# Bluetooth.net
KiCad netlist of a schematic drawn in Altium Designer
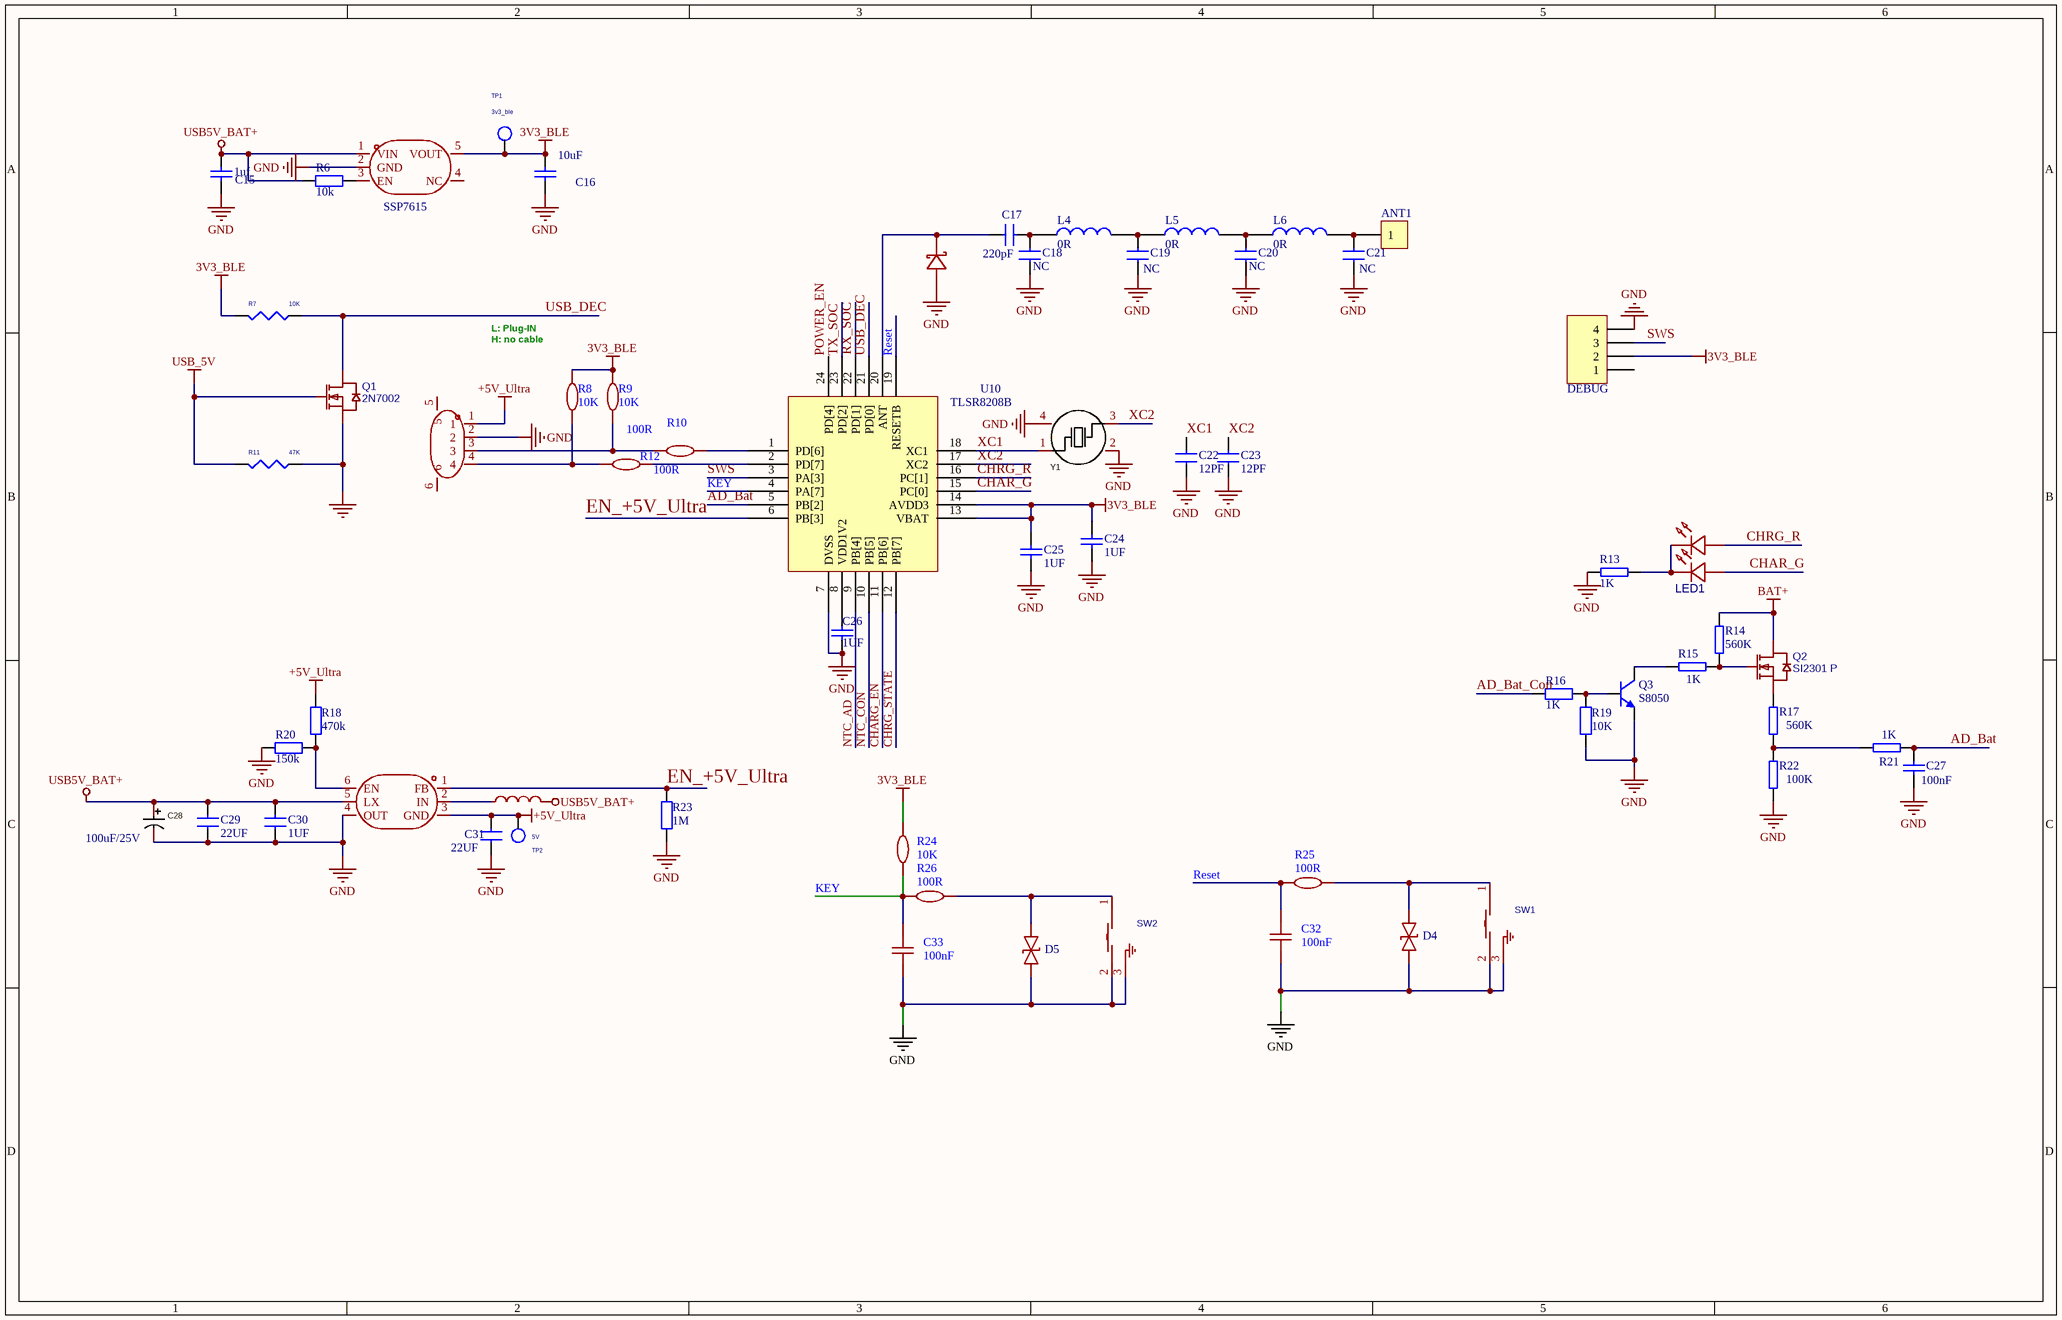
[diagram p0: Bluetooth.SchDoc]

(export (version "E")
  (design (tool "Eeschema 10.0.6"))
  (components
    (comp (ref "ANT1")
      (value "~")
      (footprint "tp")
      (description "Connector")
      (libsource (lib "*") (part "CON1"))
    )
    (comp (ref "C15")
      (value "1uf")
      (footprint "0603_C")
      (description "无极电容")
      (libsource (lib "电容电阻电感保险") (part "Cap1"))
    )
    (comp (ref "C16")
      (value "10uF")
      (footprint "0603_C")
      (description "Capacitor")
      (fields (field (name "PUBLISHER") "Altium Limited"))
      (libsource (lib "*") (part "Cap"))
    )
    (comp (ref "C17")
      (value "220pF")
      (footprint "0402_c")
      (description "Capacitor")
      (libsource (lib "*") (part "CAP"))
    )
    (comp (ref "C18")
      (value "NC")
      (footprint "0402_C")
      (description "Capacitor")
      (libsource (lib "*") (part "CAP"))
    )
    (comp (ref "C19")
      (value "NC")
      (footprint "0402_C")
      (description "Capacitor")
      (libsource (lib "*") (part "CAP"))
    )
    (comp (ref "C20")
      (value "NC")
      (footprint "0402_C")
      (description "Capacitor")
      (libsource (lib "*") (part "CAP"))
    )
    (comp (ref "C21")
      (value "NC")
      (footprint "0402_C")
      (description "Capacitor")
      (libsource (lib "*") (part "CAP"))
    )
    (comp (ref "C22")
      (value "12PF")
      (footprint "0603_c")
      (description "Capacitor")
      (libsource (lib "*") (part "CAP"))
    )
    (comp (ref "C23")
      (value "12PF")
      (footprint "0603_c")
      (description "Capacitor")
      (libsource (lib "*") (part "CAP"))
    )
    (comp (ref "C24") (value "1UF") (footprint "0603_c") (libsource (lib "DIY") (part "CAP")))
    (comp (ref "C25") (value "1UF") (footprint "0603_c") (libsource (lib "DIY") (part "CAP")))
    (comp (ref "C26") (value "1UF") (footprint "0603_c") (libsource (lib "DIY") (part "CAP")))
    (comp (ref "C27") (value "100nF") (footprint "c0402") (libsource (lib "DIY") (part "CAP")))
    (comp (ref "C28")
      (value "100uF/25V")
      (footprint "SMD 6.3*5.4 电解")
      (fields (field (name "MANUFACTURER PART") "RVT1A221M0605"))
      (libsource (lib "altium-import") (part "root_0_RVT1A221M0605_C72494_"))
    )
    (comp (ref "C29")
      (value "22UF")
      (footprint "0805_c")
      (description "Capacitor")
      (libsource (lib "*") (part "CAP"))
    )
    (comp (ref "C30")
      (value "1UF")
      (footprint "0402_c")
      (description "Capacitor")
      (libsource (lib "*") (part "CAP"))
    )
    (comp (ref "C31")
      (value "22UF")
      (footprint "0805_c")
      (description "Capacitor")
      (libsource (lib "*") (part "CAP"))
    )
    (comp (ref "C32")
      (value "100nF")
      (footprint "c0402")
      (libsource (lib "altium-import") (part "root_1_CAP_0603_"))
    )
    (comp (ref "C33")
      (value "100nF")
      (footprint "c0402")
      (libsource (lib "altium-import") (part "root_1_CAP_0603_"))
    )
    (comp (ref "CON4")
      (value "Ultra")
      (footprint "CONN-SMD_4P-P1.25_LT")
      (libsource (lib "altium-import") (part "root_0_mirrored_HC-1.25-4PLT_"))
    )
    (comp (ref "D3")
      (value "SE6V3LHN102T 6.3v单向")
      (footprint "0402-D")
      (libsource (lib "altium-import") (part "root_3_TPNSR05F20NXT5G_"))
    )
    (comp (ref "D4")
      (value "LESD5Z5.0CT1G")
      (footprint "SOD-523_L1.2-W0.8-LS1.6-BI")
      (libsource (lib "altium-import") (part "root_1_LESD5Z5.0CT1G_"))
    )
    (comp (ref "D5")
      (value "LESD5Z5.0CT1G")
      (footprint "SOD-523_L1.2-W0.8-LS1.6-BI")
      (libsource (lib "altium-import") (part "root_1_LESD5Z5.0CT1G_"))
    )
    (comp (ref "L4") (value "0R") (footprint "0402_R") (libsource (lib "*") (part "INDUCTOR")))
    (comp (ref "L5") (value "0R") (footprint "0402_R") (libsource (lib "*") (part "INDUCTOR")))
    (comp (ref "L6") (value "0R") (footprint "0402_R") (libsource (lib "*") (part "INDUCTOR")))
    (comp (ref "L7")
      (value "SLW3012P1R5MST SMD3.0*3.0")
      (footprint "IND-SMD_L3.0-W3.0")
      (libsource (lib "altium-import") (part "root_0_SLW3012P1R5MST_"))
    )
    (comp (ref "LED1")
      (value "*")
      (footprint "LED-SMD_4P-L3.2-W1.6-TL_XL-3216SURUGC")
      (libsource (lib "altium-import") (part "root_0_TJ-S2012SW8TCGLC2R2G-A5_"))
    )
    (comp (ref "P1")
      (value "DEBUG")
      (footprint "SIP4-2.54")
      (description "Header, 4-Pin")
      (fields (field (name "PUBLISHER") "Altium Limited"))
      (libsource (lib "Miscellaneous Connectors") (part "Header 4"))
    )
    (comp (ref "Q1")
      (value "2N7002")
      (footprint "SOT-23")
      (fields
        (field (name "BOM_SUPPLIER PART") "C2890442")
        (field (name "BOM_MANUFACTURER PART") "JMTL3400A")
        (field (name "CONTRIBUTOR") "LCSC")
      )
      (libsource (lib "altium-import") (part "root_0_JMTL3400A_"))
    )
    (comp (ref "Q2")
      (value "SI2301 P")
      (footprint "SOT-23")
      (fields
        (field (name "BOM_SUPPLIER PART") "C2890442")
        (field (name "BOM_MANUFACTURER PART") "JMTL3400A")
        (field (name "CONTRIBUTOR") "LCSC")
      )
      (libsource (lib "") (part "root_0_JMTL3400A__1"))
    )
    (comp (ref "Q3")
      (value "S8050")
      (footprint "SOT-23(SOT-23-3)")
      (description "NPN三极管")
      (libsource (lib "二三极管mos可控硅") (part "NPN_sot23"))
    )
    (comp (ref "R6")
      (value "10k")
      (footprint "R0402")
      (description "Resistor")
      (fields (field (name "PUBLISHER") "Altium Limited"))
      (libsource (lib "") (part "Res2_3"))
    )
    (comp (ref "R7") (value "10K") (footprint "R0402") (libsource (lib "*") (part "R_Dup2")))
    (comp (ref "R8")
      (value "10K")
      (footprint "R0402")
      (libsource (lib "altium-import") (part "root_3_Res_0603_"))
    )
    (comp (ref "R9")
      (value "10K")
      (footprint "R0402")
      (libsource (lib "altium-import") (part "root_3_Res_0603_"))
    )
    (comp (ref "R10")
      (value "100R")
      (footprint "R0402")
      (libsource (lib "altium-import") (part "root_2_Res_0603_"))
    )
    (comp (ref "R11") (value "47K") (footprint "R0402") (libsource (lib "*") (part "R_Dup2")))
    (comp (ref "R12")
      (value "100R")
      (footprint "R0402")
      (libsource (lib "altium-import") (part "root_2_Res_0603_"))
    )
    (comp (ref "R13") (value "1K") (footprint "0603_R") (libsource (lib "DIY") (part "RES")))
    (comp (ref "R14") (value "560K") (footprint "R0402") (libsource (lib "") (part "RES_1")))
    (comp (ref "R15") (value "1K") (footprint "R0402") (libsource (lib "*") (part "RES")))
    (comp (ref "R16")
      (value "1K")
      (footprint "R0402")
      (description "Resistor")
      (fields (field (name "PUBLISHER") "Altium Limited"))
      (libsource (lib "") (part "Res2_1"))
    )
    (comp (ref "R17") (value "560K") (footprint "R0402") (libsource (lib "DIY") (part "RES")))
    (comp (ref "R18")
      (value "470k")
      (footprint "0402_r")
      (description "Resistor")
      (fields (field (name "PUBLISHER") "Altium Limited"))
      (libsource (lib "") (part "Res2_2"))
    )
    (comp (ref "R19")
      (value "10K")
      (footprint "R0402")
      (description "Resistor")
      (fields (field (name "PUBLISHER") "Altium Limited"))
      (libsource (lib "") (part "Res2_3"))
    )
    (comp (ref "R20")
      (value "150k")
      (footprint "0402_r")
      (description "Resistor")
      (fields (field (name "PUBLISHER") "Altium Limited"))
      (libsource (lib "*") (part "Res2"))
    )
    (comp (ref "R21") (value "1K") (footprint "R0402") (libsource (lib "DIY") (part "RES")))
    (comp (ref "R22") (value "100K") (footprint "R0402") (libsource (lib "DIY") (part "RES")))
    (comp (ref "R23")
      (value "1M")
      (footprint "0402_r")
      (description "Resistor")
      (fields (field (name "PUBLISHER") "Altium Limited"))
      (libsource (lib "") (part "Res2_2"))
    )
    (comp (ref "R24")
      (value "10K")
      (footprint "R0402")
      (libsource (lib "altium-import") (part "root_1_Res_0603_"))
    )
    (comp (ref "R25")
      (value "100R")
      (footprint "R0402")
      (libsource (lib "altium-import") (part "root_2_Res_0603_"))
    )
    (comp (ref "R26")
      (value "100R")
      (footprint "R0402")
      (libsource (lib "altium-import") (part "root_2_Res_0603_"))
    )
    (comp (ref "SW1")
      (value "Reset")
      (footprint "SMD-KEY-3")
      (libsource (lib "altium-import") (part "root_1_K2-1109SE-I4SW-04_"))
    )
    (comp (ref "SW2")
      (value "OnOff")
      (footprint "SMD-KEY-3")
      (libsource (lib "altium-import") (part "root_1_K2-1109SE-I4SW-04_"))
    )
    (comp (ref "TP1") (value "3v3_ble") (footprint "TP") (libsource (lib "*") (part "T POINT R")))
    (comp (ref "TP2") (value "5V") (footprint "TP") (libsource (lib "*") (part "T POINT R")))
    (comp (ref "U2")
      (value "SSP7615")
      (footprint "SOT-23-5")
      (libsource (lib "altium-import") (part "root_0_SSP7615-33M5R_"))
    )
    (comp (ref "U3")
      (value "SY7069ADC")
      (footprint "SOT-23-6")
      (libsource (lib "altium-import") (part "root_0_mirrored_SY7069ADC_"))
    )
    (comp (ref "U10")
      (value "TLSR8208B")
      (footprint "QFN-24-EP(4*4)")
      (libsource (lib "MyLib") (part "TLSR8208B"))
    )
    (comp (ref "Y1")
      (value "24MHz +-20PPM")
      (footprint "CRYSTAL-SMD_4P-L3.2-W2.5")
      (fields (field (name "MANUFACTURER PART") "TAXM13.56M4RLBCCT2T"))
      (libsource (lib "altium-import") (part "root_0_TAXM13.56M4RLBCCT2T_"))
    )
  )
  (nets
    (net (code "1") (name "+5V_Ultra") (class "Default")
      (node (ref "C31") (pin "2") (pinfunction "2_2") (pintype "passive"))
      (node (ref "CON4") (pin "1") (pinfunction "1_1") (pintype "passive"))
      (node (ref "R18") (pin "2") (pinfunction "2_2") (pintype "passive"))
      (node (ref "TP2") (pin "1") (pinfunction "TP_1") (pintype "passive"))
      (node (ref "U3") (pin "3") (pinfunction "GND_3") (pintype "passive"))
    )
    (net (code "2") (name "/AD_Bat") (class "Default")
      (node (ref "C27") (pin "2") (pintype "passive"))
      (node (ref "R21") (pin "1") (pinfunction "1_1") (pintype "passive"))
      (node (ref "U10") (pin "5") (pinfunction "PB[2]_5") (pintype "passive"))
    )
    (net (code "3") (name "/AD_Bat_Con") (class "Default")
      (node (ref "R16") (pin "2") (pinfunction "2_2") (pintype "passive"))
    )
    (net (code "4") (name "/CHARG_EN") (class "Default")
      (node (ref "U10") (pin "11") (pinfunction "PB[6]_11") (pintype "passive"))
    )
    (net (code "5") (name "/CHAR_G") (class "Default")
      (node (ref "LED1") (pin "3") (pinfunction "A_3") (pintype "passive"))
      (node (ref "U10") (pin "15") (pinfunction "PC[0]_15") (pintype "passive"))
    )
    (net (code "6") (name "/CHRG_R") (class "Default")
      (node (ref "LED1") (pin "1") (pinfunction "A_1") (pintype "passive"))
      (node (ref "U10") (pin "16") (pinfunction "PC[1]_16") (pintype "passive"))
    )
    (net (code "7") (name "/CHRG_STATE") (class "Default")
      (node (ref "U10") (pin "12") (pinfunction "PB[7]_12") (pintype "passive"))
    )
    (net (code "8") (name "/EN_+5V_Ultra") (class "Default")
      (node (ref "R23") (pin "2") (pinfunction "2_2") (pintype "passive"))
      (node (ref "U10") (pin "6") (pinfunction "PB[3]_6") (pintype "passive"))
      (node (ref "U3") (pin "1") (pinfunction "FB_1") (pintype "passive"))
    )
    (net (code "9") (name "/KEY") (class "Default")
      (node (ref "C33") (pin "2") (pinfunction "2_2") (pintype "passive"))
      (node (ref "R24") (pin "1") (pinfunction "1_1") (pintype "passive"))
      (node (ref "R26") (pin "2") (pinfunction "2_2") (pintype "passive"))
      (node (ref "U10") (pin "4") (pinfunction "PA[7]_4") (pintype "passive"))
    )
    (net (code "10") (name "/NTC_AD") (class "Default")
      (node (ref "U10") (pin "9") (pinfunction "PB[4]_9") (pintype "passive"))
    )
    (net (code "11") (name "/NTC_CON") (class "Default")
      (node (ref "U10") (pin "10") (pinfunction "PB[5]_10") (pintype "passive"))
    )
    (net (code "12") (name "/POWER_EN") (class "Default")
      (node (ref "U10") (pin "24") (pinfunction "PD[4]_24") (pintype "passive"))
    )
    (net (code "13") (name "/RX_SOC") (class "Default")
      (node (ref "U10") (pin "22") (pinfunction "PD[1]_22") (pintype "passive"))
    )
    (net (code "14") (name "/Reset") (class "Default")
      (node (ref "C32") (pin "2") (pinfunction "2_2") (pintype "passive"))
      (node (ref "R25") (pin "2") (pinfunction "2_2") (pintype "passive"))
      (node (ref "U10") (pin "19") (pinfunction "RESETB_19") (pintype "passive"))
    )
    (net (code "15") (name "/SWS") (class "Default")
      (node (ref "P1") (pin "3") (pinfunction "3_3") (pintype "passive"))
      (node (ref "U10") (pin "3") (pinfunction "PA[3]_3") (pintype "passive"))
    )
    (net (code "16") (name "/TX_SOC") (class "Default")
      (node (ref "U10") (pin "23") (pinfunction "PD[2]_23") (pintype "passive"))
    )
    (net (code "17") (name "/USB_DEC") (class "Default")
      (node (ref "Q1") (pin "3") (pinfunction "D_3") (pintype "passive"))
      (node (ref "R7") (pin "2") (pinfunction "2_2") (pintype "passive"))
      (node (ref "U10") (pin "21") (pinfunction "PD[0]_21") (pintype "passive"))
    )
    (net (code "18") (name "/XC1") (class "Default")
      (node (ref "C22") (pin "2") (pinfunction "2_2") (pintype "passive"))
      (node (ref "U10") (pin "18") (pinfunction "XC1_18") (pintype "passive"))
      (node (ref "Y1") (pin "1") (pinfunction "OSC1_1") (pintype "passive"))
    )
    (net (code "19") (name "/XC2") (class "Default")
      (node (ref "C23") (pin "2") (pinfunction "2_2") (pintype "passive"))
      (node (ref "U10") (pin "17") (pinfunction "XC2_17") (pintype "passive"))
      (node (ref "Y1") (pin "3") (pinfunction "OSC2_3") (pintype "passive"))
    )
    (net (code "20") (name "3V3_BLE") (class "Default")
      (node (ref "C16") (pin "2") (pinfunction "2_2") (pintype "passive"))
      (node (ref "C24") (pin "1") (pintype "passive"))
      (node (ref "C25") (pin "1") (pintype "passive"))
      (node (ref "P1") (pin "2") (pinfunction "2_2") (pintype "passive"))
      (node (ref "R24") (pin "2") (pinfunction "2_2") (pintype "passive"))
      (node (ref "R7") (pin "1") (pinfunction "1_1") (pintype "passive"))
      (node (ref "R8") (pin "1") (pinfunction "1_1") (pintype "passive"))
      (node (ref "R9") (pin "1") (pinfunction "1_1") (pintype "passive"))
      (node (ref "TP1") (pin "1") (pinfunction "TP_1") (pintype "passive"))
      (node (ref "U10") (pin "13") (pinfunction "VBAT_13") (pintype "passive"))
      (node (ref "U10") (pin "14") (pinfunction "AVDD3_14") (pintype "passive"))
      (node (ref "U2") (pin "5") (pinfunction "VOUT_5") (pintype "passive"))
    )
    (net (code "21") (name "BAT+") (class "Default")
      (node (ref "Q2") (pin "2") (pinfunction "D_2") (pintype "passive"))
      (node (ref "R14") (pin "1") (pintype "passive"))
    )
    (net (code "22") (name "GND") (class "Default")
      (node (ref "C15") (pin "1") (pinfunction "1_1") (pintype "passive"))
      (node (ref "C16") (pin "1") (pinfunction "1_1") (pintype "passive"))
      (node (ref "C18") (pin "1") (pinfunction "1_1") (pintype "passive"))
      (node (ref "C19") (pin "1") (pinfunction "1_1") (pintype "passive"))
      (node (ref "C20") (pin "1") (pinfunction "1_1") (pintype "passive"))
      (node (ref "C21") (pin "1") (pinfunction "1_1") (pintype "passive"))
      (node (ref "C22") (pin "1") (pinfunction "1_1") (pintype "passive"))
      (node (ref "C23") (pin "1") (pinfunction "1_1") (pintype "passive"))
      (node (ref "C24") (pin "2") (pintype "passive"))
      (node (ref "C25") (pin "2") (pintype "passive"))
      (node (ref "C26") (pin "1") (pintype "passive"))
      (node (ref "C27") (pin "1") (pintype "passive"))
      (node (ref "C28") (pin "2") (pinfunction "2_2") (pintype "passive"))
      (node (ref "C29") (pin "1") (pinfunction "1_1") (pintype "passive"))
      (node (ref "C30") (pin "1") (pinfunction "1_1") (pintype "passive"))
      (node (ref "C31") (pin "1") (pinfunction "1_1") (pintype "passive"))
      (node (ref "C32") (pin "1") (pinfunction "1_1") (pintype "passive"))
      (node (ref "C33") (pin "1") (pinfunction "1_1") (pintype "passive"))
      (node (ref "CON4") (pin "2") (pinfunction "2_2") (pintype "passive"))
      (node (ref "D3") (pin "2") (pinfunction "A_2") (pintype "passive"))
      (node (ref "D4") (pin "1") (pinfunction "1_1") (pintype "passive"))
      (node (ref "D5") (pin "1") (pinfunction "1_1") (pintype "passive"))
      (node (ref "P1") (pin "4") (pinfunction "4_4") (pintype "passive"))
      (node (ref "Q1") (pin "2") (pinfunction "S_2") (pintype "passive"))
      (node (ref "Q3") (pin "2") (pinfunction "E_2") (pintype "passive"))
      (node (ref "R11") (pin "2") (pinfunction "2_2") (pintype "passive"))
      (node (ref "R13") (pin "1") (pinfunction "1_1") (pintype "passive"))
      (node (ref "R19") (pin "1") (pinfunction "1_1") (pintype "passive"))
      (node (ref "R20") (pin "2") (pinfunction "2_2") (pintype "passive"))
      (node (ref "R22") (pin "2") (pinfunction "2_2") (pintype "passive"))
      (node (ref "R23") (pin "1") (pinfunction "1_1") (pintype "passive"))
      (node (ref "SW1") (pin "2") (pinfunction "2_2") (pintype "passive"))
      (node (ref "SW1") (pin "3") (pinfunction "3_3") (pintype "passive"))
      (node (ref "SW2") (pin "2") (pinfunction "2_2") (pintype "passive"))
      (node (ref "SW2") (pin "3") (pinfunction "3_3") (pintype "passive"))
      (node (ref "U10") (pin "7") (pinfunction "DVSS_7") (pintype "passive"))
      (node (ref "U2") (pin "2") (pinfunction "GND_2") (pintype "passive"))
      (node (ref "U3") (pin "4") (pinfunction "OUT_4") (pintype "passive"))
      (node (ref "Y1") (pin "2") (pinfunction "GND_2") (pintype "passive"))
      (node (ref "Y1") (pin "4") (pinfunction "GND_4") (pintype "passive"))
    )
    (net (code "23") (name "Net-(ANT1-Pad1)") (class "Default")
      (node (ref "ANT1") (pin "1") (pinfunction "1_1") (pintype "passive"))
      (node (ref "C21") (pin "2") (pinfunction "2_2") (pintype "passive"))
      (node (ref "L6") (pin "2") (pinfunction "2_2") (pintype "passive"))
    )
    (net (code "24") (name "Net-(C17-Pad2)") (class "Default")
      (node (ref "C17") (pin "2") (pinfunction "2_2") (pintype "passive"))
      (node (ref "C18") (pin "2") (pinfunction "2_2") (pintype "passive"))
      (node (ref "L4") (pin "1") (pinfunction "1_1") (pintype "passive"))
    )
    (net (code "25") (name "Net-(C19-Pad2)") (class "Default")
      (node (ref "C19") (pin "2") (pinfunction "2_2") (pintype "passive"))
      (node (ref "L4") (pin "2") (pinfunction "2_2") (pintype "passive"))
      (node (ref "L5") (pin "1") (pinfunction "1_1") (pintype "passive"))
    )
    (net (code "26") (name "Net-(C20-Pad2)") (class "Default")
      (node (ref "C20") (pin "2") (pinfunction "2_2") (pintype "passive"))
      (node (ref "L5") (pin "2") (pinfunction "2_2") (pintype "passive"))
      (node (ref "L6") (pin "1") (pinfunction "1_1") (pintype "passive"))
    )
    (net (code "27") (name "Net-(CON4-Pad3)") (class "Default")
      (node (ref "CON4") (pin "3") (pinfunction "3_3") (pintype "passive"))
      (node (ref "R10") (pin "2") (pinfunction "2_2") (pintype "passive"))
      (node (ref "R9") (pin "2") (pinfunction "2_2") (pintype "passive"))
    )
    (net (code "28") (name "Net-(CON4-Pad4)") (class "Default")
      (node (ref "CON4") (pin "4") (pinfunction "4_4") (pintype "passive"))
      (node (ref "R12") (pin "2") (pinfunction "2_2") (pintype "passive"))
      (node (ref "R8") (pin "2") (pinfunction "2_2") (pintype "passive"))
    )
    (net (code "29") (name "Net-(D3-C)") (class "Default")
      (node (ref "C17") (pin "1") (pinfunction "1_1") (pintype "passive"))
      (node (ref "D3") (pin "1") (pinfunction "C_1") (pintype "passive"))
      (node (ref "U10") (pin "20") (pinfunction "ANT_20") (pintype "passive"))
    )
    (net (code "30") (name "Net-(D4-Pad2)") (class "Default")
      (node (ref "D4") (pin "2") (pinfunction "2_2") (pintype "passive"))
      (node (ref "R25") (pin "1") (pinfunction "1_1") (pintype "passive"))
      (node (ref "SW1") (pin "1") (pinfunction "1_1") (pintype "passive"))
    )
    (net (code "31") (name "Net-(D5-Pad2)") (class "Default")
      (node (ref "D5") (pin "2") (pinfunction "2_2") (pintype "passive"))
      (node (ref "R26") (pin "1") (pinfunction "1_1") (pintype "passive"))
      (node (ref "SW2") (pin "1") (pinfunction "1_1") (pintype "passive"))
    )
    (net (code "32") (name "Net-(LED1-K-Pad2)") (class "Default")
      (node (ref "LED1") (pin "2") (pinfunction "K_2") (pintype "passive"))
      (node (ref "LED1") (pin "4") (pinfunction "K_4") (pintype "passive"))
      (node (ref "R13") (pin "2") (pinfunction "2_2") (pintype "passive"))
    )
    (net (code "33") (name "Net-(Q2-G)") (class "Default")
      (node (ref "Q2") (pin "1") (pinfunction "G_1") (pintype "passive"))
      (node (ref "R14") (pin "2") (pintype "passive"))
      (node (ref "R15") (pin "1") (pintype "passive"))
    )
    (net (code "34") (name "Net-(Q2-S)") (class "Default")
      (node (ref "Q2") (pin "3") (pinfunction "S_3") (pintype "passive"))
      (node (ref "R17") (pin "1") (pinfunction "1_1") (pintype "passive"))
    )
    (net (code "35") (name "Net-(Q3-B)") (class "Default")
      (node (ref "Q3") (pin "1") (pinfunction "B_1") (pintype "passive"))
      (node (ref "R16") (pin "1") (pinfunction "1_1") (pintype "passive"))
      (node (ref "R19") (pin "2") (pinfunction "2_2") (pintype "passive"))
    )
    (net (code "36") (name "Net-(Q3-C)") (class "Default")
      (node (ref "Q3") (pin "3") (pinfunction "C_3") (pintype "passive"))
      (node (ref "R15") (pin "2") (pintype "passive"))
    )
    (net (code "37") (name "Net-(R17-Pad2)") (class "Default")
      (node (ref "R17") (pin "2") (pinfunction "2_2") (pintype "passive"))
      (node (ref "R21") (pin "2") (pinfunction "2_2") (pintype "passive"))
      (node (ref "R22") (pin "1") (pinfunction "1_1") (pintype "passive"))
    )
    (net (code "38") (name "Net-(U2-EN)") (class "Default")
      (node (ref "R6") (pin "2") (pinfunction "2_2") (pintype "passive"))
      (node (ref "U2") (pin "3") (pinfunction "EN_3") (pintype "passive"))
    )
    (net (code "39") (name "Net-(U3-EN)") (class "Default")
      (node (ref "R18") (pin "1") (pinfunction "1_1") (pintype "passive"))
      (node (ref "R20") (pin "1") (pinfunction "1_1") (pintype "passive"))
      (node (ref "U3") (pin "6") (pinfunction "EN_6") (pintype "passive"))
    )
    (net (code "40") (name "Net-(U3-IN)") (class "Default")
      (node (ref "L7") (pin "1") (pinfunction "1_1") (pintype "passive"))
      (node (ref "U3") (pin "2") (pinfunction "IN_2") (pintype "passive"))
    )
    (net (code "41") (name "Net-(U10-PD[6])") (class "Default")
      (node (ref "R10") (pin "1") (pinfunction "1_1") (pintype "passive"))
      (node (ref "U10") (pin "1") (pinfunction "PD[6]_1") (pintype "passive"))
    )
    (net (code "42") (name "Net-(U10-PD[7])") (class "Default")
      (node (ref "R12") (pin "1") (pinfunction "1_1") (pintype "passive"))
      (node (ref "U10") (pin "2") (pinfunction "PD[7]_2") (pintype "passive"))
    )
    (net (code "43") (name "Net-(U10-VDD1V2)") (class "Default")
      (node (ref "C26") (pin "2") (pintype "passive"))
      (node (ref "U10") (pin "8") (pinfunction "VDD1V2_8") (pintype "passive"))
    )
    (net (code "44") (name "USB5V_BAT+") (class "Default")
      (node (ref "C15") (pin "2") (pinfunction "2_2") (pintype "passive"))
      (node (ref "C28") (pin "1") (pinfunction "1_1") (pintype "passive"))
      (node (ref "C29") (pin "2") (pinfunction "2_2") (pintype "passive"))
      (node (ref "C30") (pin "2") (pinfunction "2_2") (pintype "passive"))
      (node (ref "L7") (pin "2") (pinfunction "2_2") (pintype "passive"))
      (node (ref "R6") (pin "1") (pinfunction "1_1") (pintype "passive"))
      (node (ref "U2") (pin "1") (pinfunction "VIN_1") (pintype "passive"))
      (node (ref "U3") (pin "5") (pinfunction "LX_5") (pintype "passive"))
    )
    (net (code "45") (name "USB_5V") (class "Default")
      (node (ref "Q1") (pin "1") (pinfunction "G_1") (pintype "passive"))
      (node (ref "R11") (pin "1") (pinfunction "1_1") (pintype "passive"))
    )
    (net (code "46") (name "unconnected-(CON4-Pad5)") (class "Default")
      (node (ref "CON4") (pin "5") (pinfunction "5_5") (pintype "passive"))
    )
    (net (code "47") (name "unconnected-(CON4-Pad6)") (class "Default")
      (node (ref "CON4") (pin "6") (pinfunction "6_6") (pintype "passive"))
    )
    (net (code "48") (name "unconnected-(P1-Pad1)") (class "Default")
      (node (ref "P1") (pin "1") (pinfunction "1_1") (pintype "passive"))
    )
    (net (code "49") (name "unconnected-(U2-NC-Pad4)") (class "Default")
      (node (ref "U2") (pin "4") (pinfunction "NC_4") (pintype "passive"))
    )
  )
)
